# 8-Kanal-DIN-OUT_V1.net
KiCad netlist of a schematic drawn in EAGLE
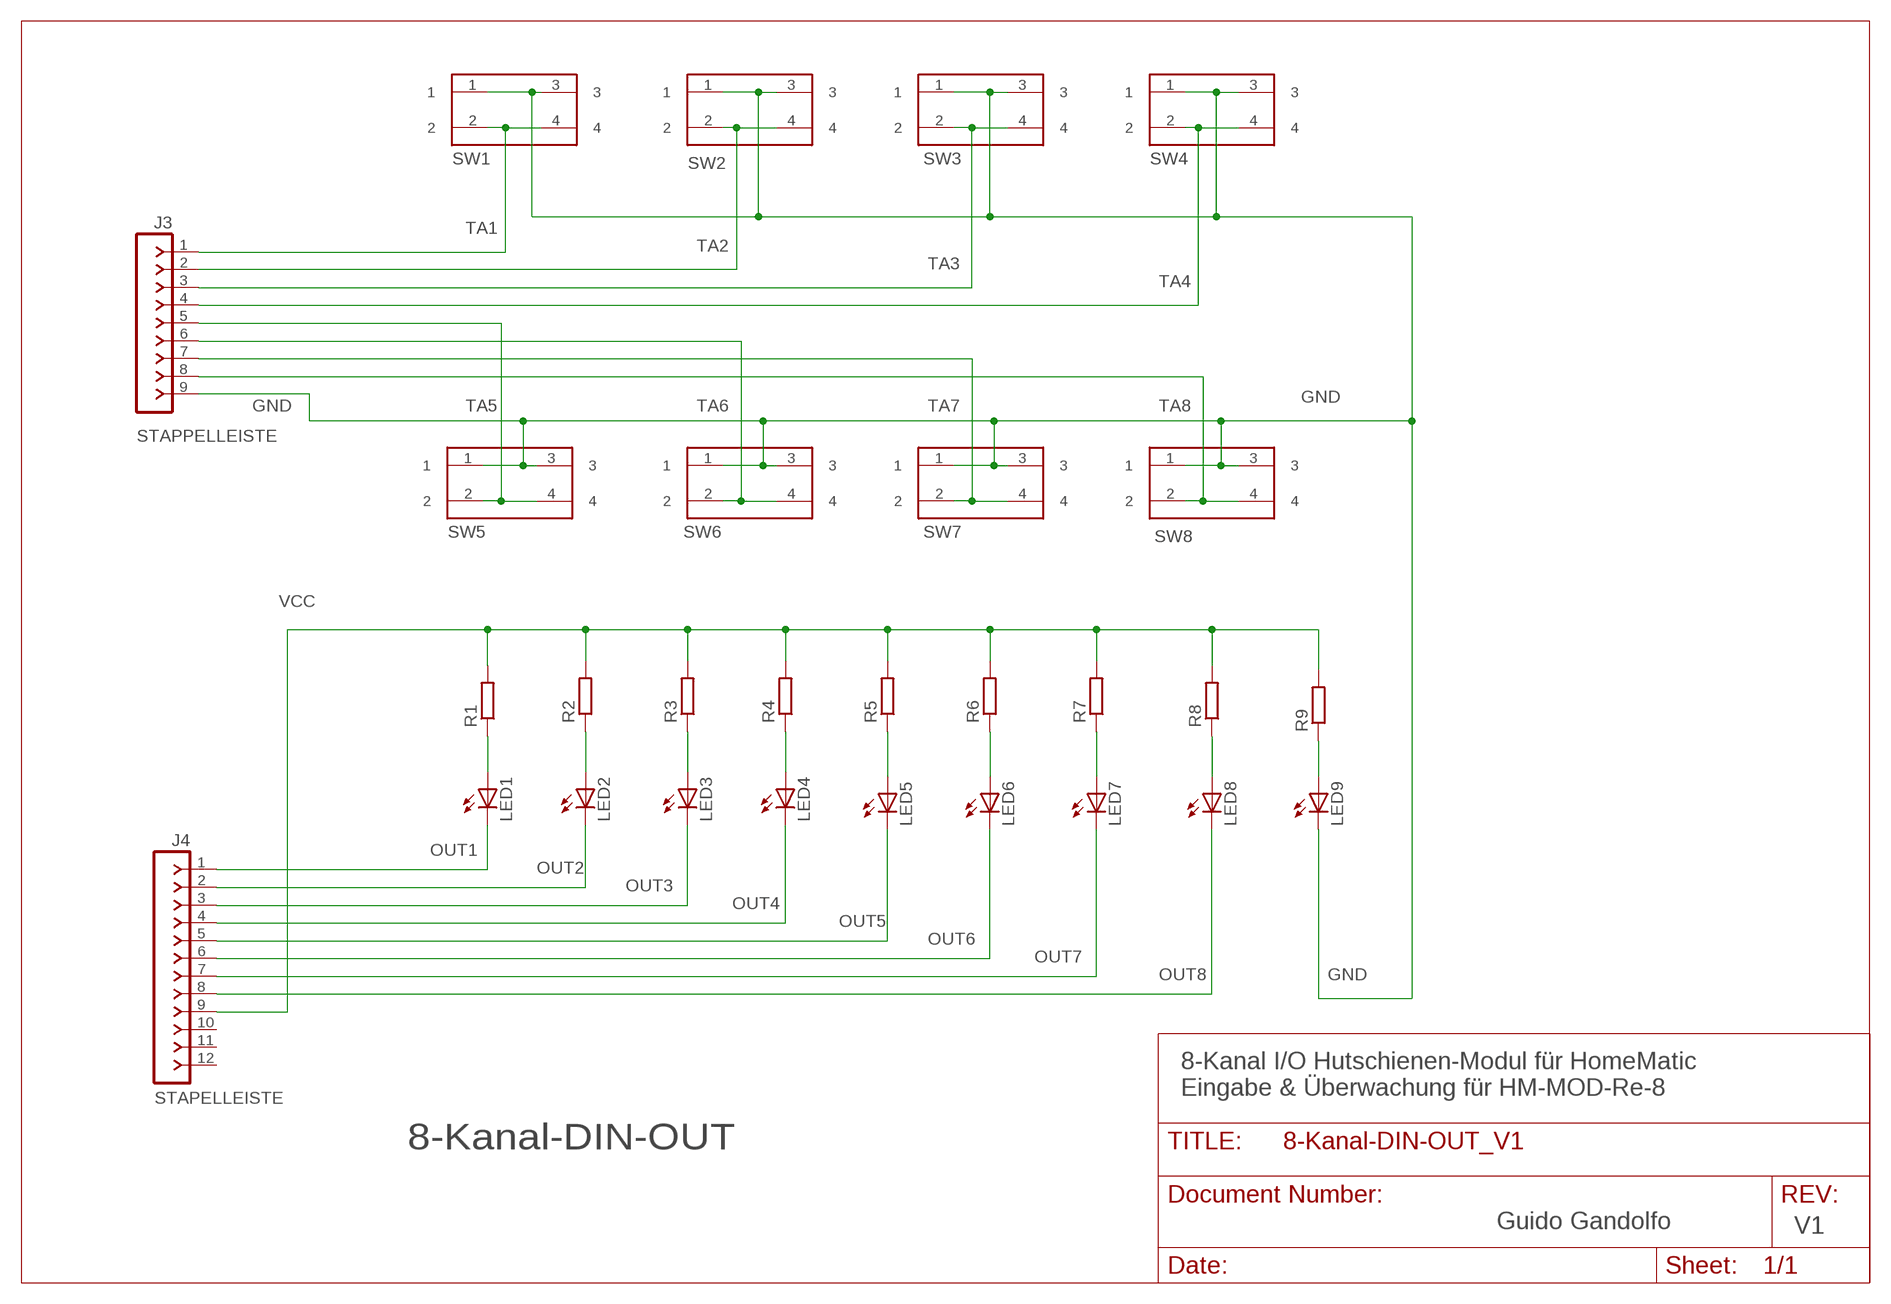
[diagram p0: schematic, sheet 1]

(export (version "E")
  (design (tool "Eeschema 10.0.6"))
  (components
    (comp (ref "J3")
      (value "STAPPELLEISTE")
      (footprint "eagle-import:SIP-100-09-40Y")
      (libsource (lib "eagle-import") (part "F-1X09-SIP-100-40Y"))
    )
    (comp (ref "J4")
      (value "STAPELLEISTE")
      (footprint "eagle-import:SIP-100-12-40Y")
      (libsource (lib "eagle-import") (part "F-1X12-SIP-100-40Y"))
    )
    (comp (ref "LED1")
      (value "LED3MM")
      (footprint "eagle-import:LED3MM")
      (libsource (lib "eagle-import") (part "LED3MM"))
    )
    (comp (ref "LED2")
      (value "LED3MM")
      (footprint "eagle-import:LED3MM")
      (libsource (lib "eagle-import") (part "LED3MM"))
    )
    (comp (ref "LED3")
      (value "LED3MM")
      (footprint "eagle-import:LED3MM")
      (libsource (lib "eagle-import") (part "LED3MM"))
    )
    (comp (ref "LED4")
      (value "LED3MM")
      (footprint "eagle-import:LED3MM")
      (libsource (lib "eagle-import") (part "LED3MM"))
    )
    (comp (ref "LED5")
      (value "LED3MM")
      (footprint "eagle-import:LED3MM")
      (libsource (lib "eagle-import") (part "LED3MM"))
    )
    (comp (ref "LED6")
      (value "LED3MM")
      (footprint "eagle-import:LED3MM")
      (libsource (lib "eagle-import") (part "LED3MM"))
    )
    (comp (ref "LED7")
      (value "LED3MM")
      (footprint "eagle-import:LED3MM")
      (libsource (lib "eagle-import") (part "LED3MM"))
    )
    (comp (ref "LED8")
      (value "LED3MM")
      (footprint "eagle-import:LED3MM")
      (libsource (lib "eagle-import") (part "LED3MM"))
    )
    (comp (ref "LED9")
      (value "LED3MM")
      (footprint "eagle-import:LED3MM")
      (libsource (lib "eagle-import") (part "LED3MM"))
    )
    (comp (ref "R1")
      (value "R-EU_0207/2V")
      (footprint "eagle-import:0207_2V")
      (libsource (lib "eagle-import") (part "R-EU_0207/2V"))
    )
    (comp (ref "R2")
      (value "R-EU_0207/2V")
      (footprint "eagle-import:0207_2V")
      (libsource (lib "eagle-import") (part "R-EU_0207/2V"))
    )
    (comp (ref "R3")
      (value "R-EU_0207/2V")
      (footprint "eagle-import:0207_2V")
      (libsource (lib "eagle-import") (part "R-EU_0207/2V"))
    )
    (comp (ref "R4")
      (value "R-EU_0207/2V")
      (footprint "eagle-import:0207_2V")
      (libsource (lib "eagle-import") (part "R-EU_0207/2V"))
    )
    (comp (ref "R5")
      (value "R-EU_0207/2V")
      (footprint "eagle-import:0207_2V")
      (libsource (lib "eagle-import") (part "R-EU_0207/2V"))
    )
    (comp (ref "R6")
      (value "R-EU_0207/2V")
      (footprint "eagle-import:0207_2V")
      (libsource (lib "eagle-import") (part "R-EU_0207/2V"))
    )
    (comp (ref "R7")
      (value "R-EU_0207/2V")
      (footprint "eagle-import:0207_2V")
      (libsource (lib "eagle-import") (part "R-EU_0207/2V"))
    )
    (comp (ref "R8")
      (value "R-EU_0207/2V")
      (footprint "eagle-import:0207_2V")
      (libsource (lib "eagle-import") (part "R-EU_0207/2V"))
    )
    (comp (ref "R9")
      (value "R-EU_0207/2V")
      (footprint "eagle-import:0207_2V")
      (libsource (lib "eagle-import") (part "R-EU_0207/2V"))
    )
    (comp (ref "SW1")
      (value "TASTER 9305")
      (footprint "eagle-import:430156130936")
      (libsource (lib "eagle-import") (part "430156130936"))
    )
    (comp (ref "SW2")
      (value "TASTER 9305")
      (footprint "eagle-import:430156130936")
      (libsource (lib "eagle-import") (part "430156130936"))
    )
    (comp (ref "SW3")
      (value "TASTER 9305")
      (footprint "eagle-import:430156130936")
      (libsource (lib "eagle-import") (part "430156130936"))
    )
    (comp (ref "SW4")
      (value "TASTER 9305")
      (footprint "eagle-import:430156130936")
      (libsource (lib "eagle-import") (part "430156130936"))
    )
    (comp (ref "SW5")
      (value "TASTER 9305")
      (footprint "eagle-import:430156130936")
      (libsource (lib "eagle-import") (part "430156130936"))
    )
    (comp (ref "SW6")
      (value "TASTER 9305")
      (footprint "eagle-import:430156130936")
      (libsource (lib "eagle-import") (part "430156130936"))
    )
    (comp (ref "SW7")
      (value "TASTER 9305")
      (footprint "eagle-import:430156130936")
      (libsource (lib "eagle-import") (part "430156130936"))
    )
    (comp (ref "SW8")
      (value "TASTER 9305")
      (footprint "eagle-import:430156130936")
      (libsource (lib "eagle-import") (part "430156130936"))
    )
  )
  (nets
    (net (code "1") (name "/GND") (class "Default")
      (node (ref "J3") (pin "9") (pinfunction "9_9") (pintype "passive"))
      (node (ref "LED9") (pin "K") (pinfunction "C_K") (pintype "passive"))
      (node (ref "SW1") (pin "1") (pinfunction "1_1") (pintype "bidirectional"))
      (node (ref "SW1") (pin "3") (pinfunction "3_3") (pintype "bidirectional"))
      (node (ref "SW2") (pin "1") (pinfunction "1_1") (pintype "bidirectional"))
      (node (ref "SW2") (pin "3") (pinfunction "3_3") (pintype "bidirectional"))
      (node (ref "SW3") (pin "1") (pinfunction "1_1") (pintype "bidirectional"))
      (node (ref "SW3") (pin "3") (pinfunction "3_3") (pintype "bidirectional"))
      (node (ref "SW4") (pin "1") (pinfunction "1_1") (pintype "bidirectional"))
      (node (ref "SW4") (pin "3") (pinfunction "3_3") (pintype "bidirectional"))
      (node (ref "SW5") (pin "1") (pinfunction "1_1") (pintype "bidirectional"))
      (node (ref "SW5") (pin "3") (pinfunction "3_3") (pintype "bidirectional"))
      (node (ref "SW6") (pin "1") (pinfunction "1_1") (pintype "bidirectional"))
      (node (ref "SW6") (pin "3") (pinfunction "3_3") (pintype "bidirectional"))
      (node (ref "SW7") (pin "1") (pinfunction "1_1") (pintype "bidirectional"))
      (node (ref "SW7") (pin "3") (pinfunction "3_3") (pintype "bidirectional"))
      (node (ref "SW8") (pin "1") (pinfunction "1_1") (pintype "bidirectional"))
      (node (ref "SW8") (pin "3") (pinfunction "3_3") (pintype "bidirectional"))
    )
    (net (code "2") (name "/OUT1") (class "Default")
      (node (ref "J4") (pin "1") (pinfunction "1_1") (pintype "passive"))
      (node (ref "LED1") (pin "K") (pinfunction "C_K") (pintype "passive"))
    )
    (net (code "3") (name "/OUT2") (class "Default")
      (node (ref "J4") (pin "2") (pinfunction "2_2") (pintype "passive"))
      (node (ref "LED2") (pin "K") (pinfunction "C_K") (pintype "passive"))
    )
    (net (code "4") (name "/OUT3") (class "Default")
      (node (ref "J4") (pin "3") (pinfunction "3_3") (pintype "passive"))
      (node (ref "LED3") (pin "K") (pinfunction "C_K") (pintype "passive"))
    )
    (net (code "5") (name "/OUT4") (class "Default")
      (node (ref "J4") (pin "4") (pinfunction "4_4") (pintype "passive"))
      (node (ref "LED4") (pin "K") (pinfunction "C_K") (pintype "passive"))
    )
    (net (code "6") (name "/OUT5") (class "Default")
      (node (ref "J4") (pin "5") (pinfunction "5_5") (pintype "passive"))
      (node (ref "LED5") (pin "K") (pinfunction "C_K") (pintype "passive"))
    )
    (net (code "7") (name "/OUT6") (class "Default")
      (node (ref "J4") (pin "6") (pinfunction "6_6") (pintype "passive"))
      (node (ref "LED6") (pin "K") (pinfunction "C_K") (pintype "passive"))
    )
    (net (code "8") (name "/OUT7") (class "Default")
      (node (ref "J4") (pin "7") (pinfunction "7_7") (pintype "passive"))
      (node (ref "LED7") (pin "K") (pinfunction "C_K") (pintype "passive"))
    )
    (net (code "9") (name "/OUT8") (class "Default")
      (node (ref "J4") (pin "8") (pinfunction "8_8") (pintype "passive"))
      (node (ref "LED8") (pin "K") (pinfunction "C_K") (pintype "passive"))
    )
    (net (code "10") (name "/TA1") (class "Default")
      (node (ref "J3") (pin "1") (pinfunction "1_1") (pintype "passive"))
      (node (ref "SW1") (pin "2") (pinfunction "2_2") (pintype "bidirectional"))
      (node (ref "SW1") (pin "4") (pinfunction "4_4") (pintype "bidirectional"))
    )
    (net (code "11") (name "/TA2") (class "Default")
      (node (ref "J3") (pin "2") (pinfunction "2_2") (pintype "passive"))
      (node (ref "SW2") (pin "2") (pinfunction "2_2") (pintype "bidirectional"))
      (node (ref "SW2") (pin "4") (pinfunction "4_4") (pintype "bidirectional"))
    )
    (net (code "12") (name "/TA3") (class "Default")
      (node (ref "J3") (pin "3") (pinfunction "3_3") (pintype "passive"))
      (node (ref "SW3") (pin "2") (pinfunction "2_2") (pintype "bidirectional"))
      (node (ref "SW3") (pin "4") (pinfunction "4_4") (pintype "bidirectional"))
    )
    (net (code "13") (name "/TA4") (class "Default")
      (node (ref "J3") (pin "4") (pinfunction "4_4") (pintype "passive"))
      (node (ref "SW4") (pin "2") (pinfunction "2_2") (pintype "bidirectional"))
      (node (ref "SW4") (pin "4") (pinfunction "4_4") (pintype "bidirectional"))
    )
    (net (code "14") (name "/TA5") (class "Default")
      (node (ref "J3") (pin "5") (pinfunction "5_5") (pintype "passive"))
      (node (ref "SW5") (pin "2") (pinfunction "2_2") (pintype "bidirectional"))
      (node (ref "SW5") (pin "4") (pinfunction "4_4") (pintype "bidirectional"))
    )
    (net (code "15") (name "/TA6") (class "Default")
      (node (ref "J3") (pin "6") (pinfunction "6_6") (pintype "passive"))
      (node (ref "SW6") (pin "2") (pinfunction "2_2") (pintype "bidirectional"))
      (node (ref "SW6") (pin "4") (pinfunction "4_4") (pintype "bidirectional"))
    )
    (net (code "16") (name "/TA7") (class "Default")
      (node (ref "J3") (pin "7") (pinfunction "7_7") (pintype "passive"))
      (node (ref "SW7") (pin "2") (pinfunction "2_2") (pintype "bidirectional"))
      (node (ref "SW7") (pin "4") (pinfunction "4_4") (pintype "bidirectional"))
    )
    (net (code "17") (name "/TA8") (class "Default")
      (node (ref "J3") (pin "8") (pinfunction "8_8") (pintype "passive"))
      (node (ref "SW8") (pin "2") (pinfunction "2_2") (pintype "bidirectional"))
      (node (ref "SW8") (pin "4") (pinfunction "4_4") (pintype "bidirectional"))
    )
    (net (code "18") (name "/VCC") (class "Default")
      (node (ref "J4") (pin "9") (pinfunction "9_9") (pintype "passive"))
      (node (ref "R1") (pin "2") (pinfunction "2_2") (pintype "passive"))
      (node (ref "R2") (pin "2") (pinfunction "2_2") (pintype "passive"))
      (node (ref "R3") (pin "2") (pinfunction "2_2") (pintype "passive"))
      (node (ref "R4") (pin "2") (pinfunction "2_2") (pintype "passive"))
      (node (ref "R5") (pin "2") (pinfunction "2_2") (pintype "passive"))
      (node (ref "R6") (pin "2") (pinfunction "2_2") (pintype "passive"))
      (node (ref "R7") (pin "2") (pinfunction "2_2") (pintype "passive"))
      (node (ref "R8") (pin "2") (pinfunction "2_2") (pintype "passive"))
      (node (ref "R9") (pin "2") (pinfunction "2_2") (pintype "passive"))
    )
    (net (code "19") (name "Net-(LED1-PadA)") (class "Default")
      (node (ref "LED1") (pin "A") (pinfunction "A_A") (pintype "passive"))
      (node (ref "R1") (pin "1") (pinfunction "1_1") (pintype "passive"))
    )
    (net (code "20") (name "Net-(LED2-PadA)") (class "Default")
      (node (ref "LED2") (pin "A") (pinfunction "A_A") (pintype "passive"))
      (node (ref "R2") (pin "1") (pinfunction "1_1") (pintype "passive"))
    )
    (net (code "21") (name "Net-(LED3-PadA)") (class "Default")
      (node (ref "LED3") (pin "A") (pinfunction "A_A") (pintype "passive"))
      (node (ref "R3") (pin "1") (pinfunction "1_1") (pintype "passive"))
    )
    (net (code "22") (name "Net-(LED4-PadA)") (class "Default")
      (node (ref "LED4") (pin "A") (pinfunction "A_A") (pintype "passive"))
      (node (ref "R4") (pin "1") (pinfunction "1_1") (pintype "passive"))
    )
    (net (code "23") (name "Net-(LED5-PadA)") (class "Default")
      (node (ref "LED5") (pin "A") (pinfunction "A_A") (pintype "passive"))
      (node (ref "R5") (pin "1") (pinfunction "1_1") (pintype "passive"))
    )
    (net (code "24") (name "Net-(LED6-PadA)") (class "Default")
      (node (ref "LED6") (pin "A") (pinfunction "A_A") (pintype "passive"))
      (node (ref "R6") (pin "1") (pinfunction "1_1") (pintype "passive"))
    )
    (net (code "25") (name "Net-(LED7-PadA)") (class "Default")
      (node (ref "LED7") (pin "A") (pinfunction "A_A") (pintype "passive"))
      (node (ref "R7") (pin "1") (pinfunction "1_1") (pintype "passive"))
    )
    (net (code "26") (name "Net-(LED8-PadA)") (class "Default")
      (node (ref "LED8") (pin "A") (pinfunction "A_A") (pintype "passive"))
      (node (ref "R8") (pin "1") (pinfunction "1_1") (pintype "passive"))
    )
    (net (code "27") (name "Net-(LED9-PadA)") (class "Default")
      (node (ref "LED9") (pin "A") (pinfunction "A_A") (pintype "passive"))
      (node (ref "R9") (pin "1") (pinfunction "1_1") (pintype "passive"))
    )
    (net (code "28") (name "unconnected-(J4-Pad10)") (class "Default")
      (node (ref "J4") (pin "10") (pinfunction "10_10") (pintype "passive"))
    )
    (net (code "29") (name "unconnected-(J4-Pad11)") (class "Default")
      (node (ref "J4") (pin "11") (pinfunction "11_11") (pintype "passive"))
    )
    (net (code "30") (name "unconnected-(J4-Pad12)") (class "Default")
      (node (ref "J4") (pin "12") (pinfunction "12_12") (pintype "passive"))
    )
  )
)
